# TD_Toolboard_V2.net
KiCad netlist of a schematic drawn in EAGLE
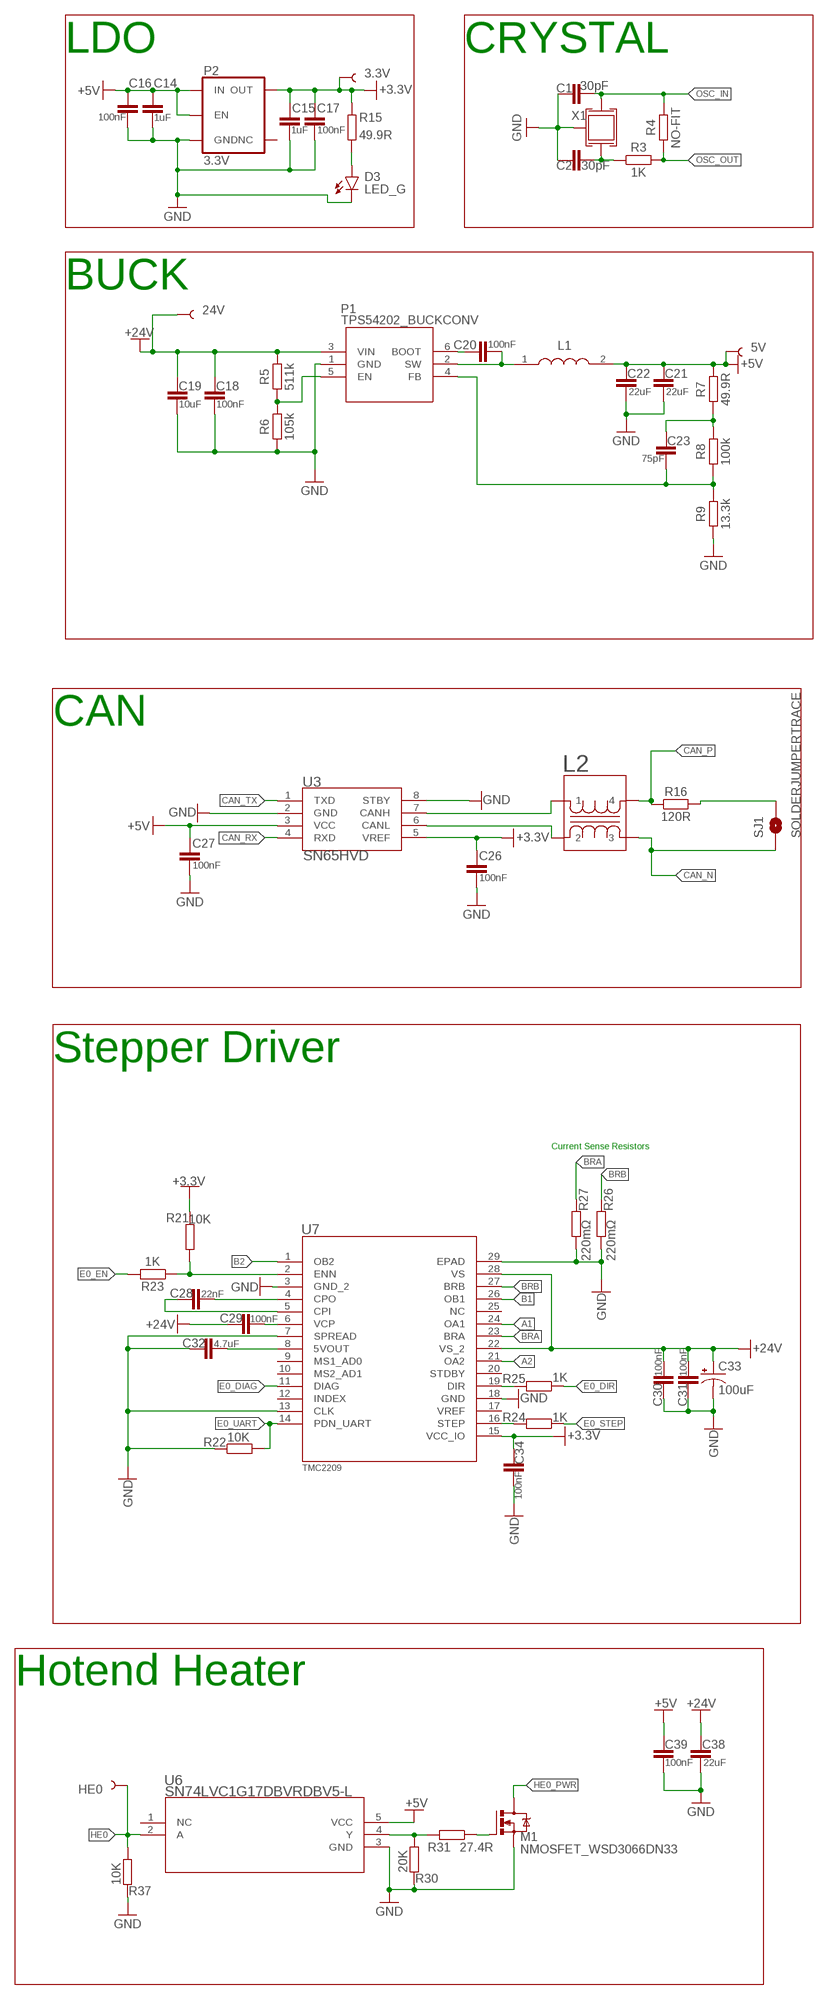
[diagram p0: schematic, sheet 1, part 1 of 2]
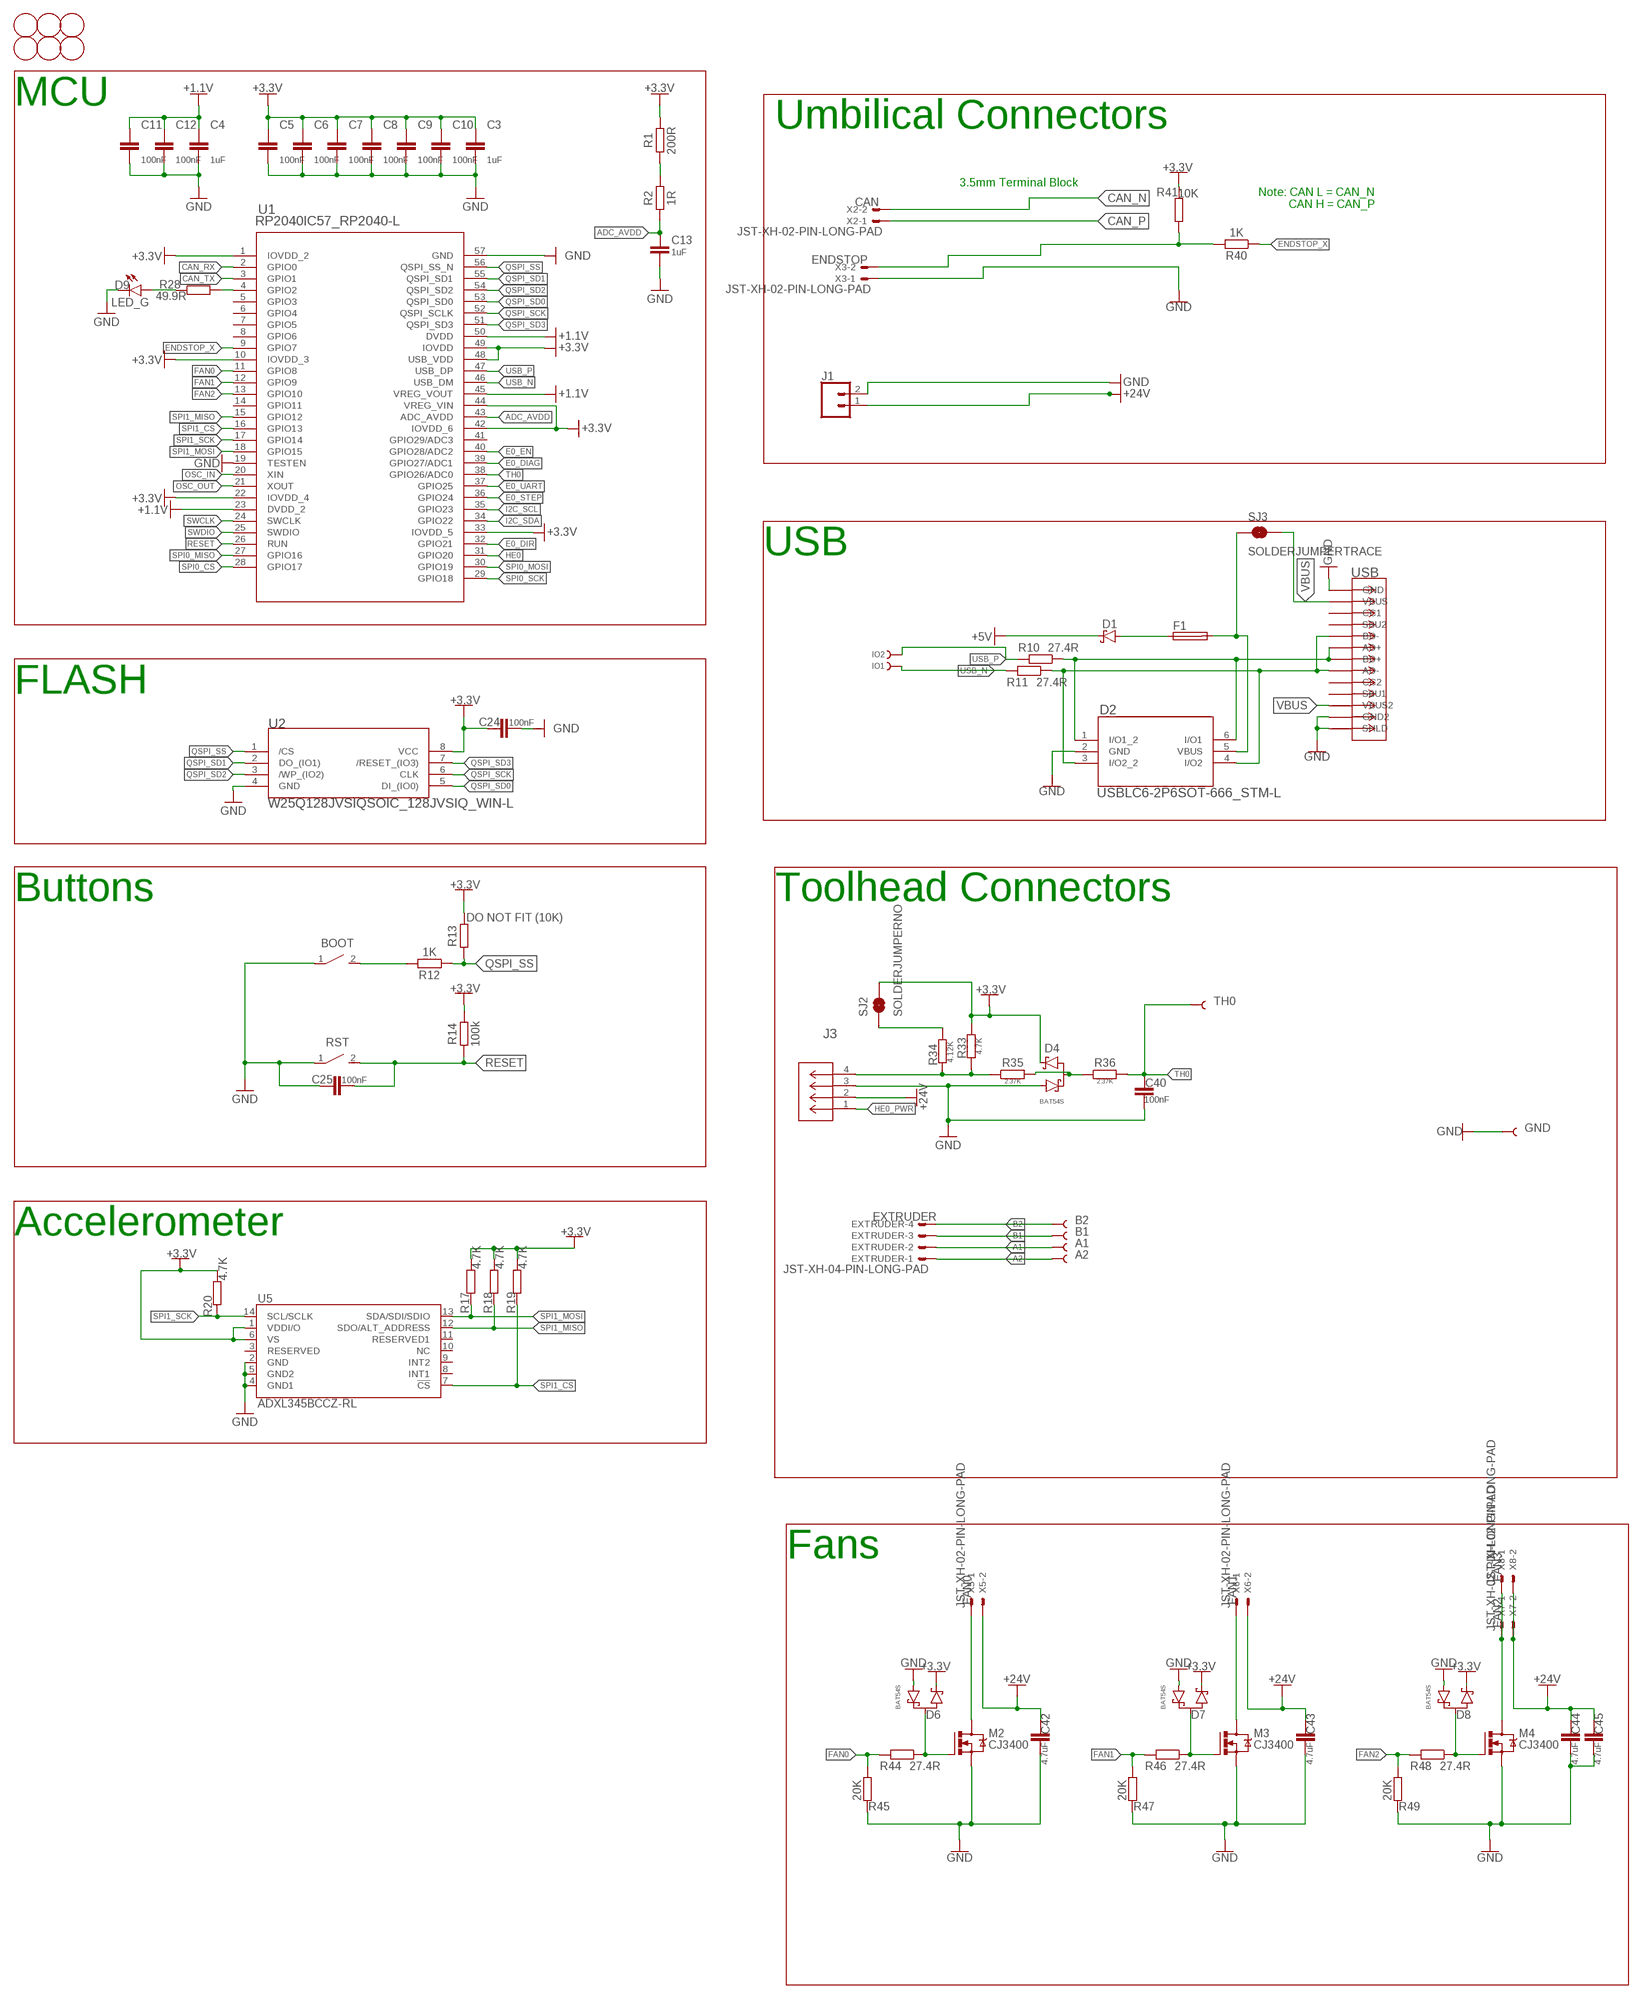
[diagram p1: schematic, sheet 1, part 2 of 2]

(export (version "E")
  (design (tool "Eeschema 10.0.6"))
  (components
    (comp (ref "3.3V")
      (value "TEST-POINT3X4")
      (footprint "eagle-import:PAD.03X.04")
      (libsource (lib "eagle-import") (part "TEST-POINT3X4"))
    )
    (comp (ref "5V")
      (value "TEST-POINT3X4")
      (footprint "eagle-import:PAD.03X.04")
      (libsource (lib "eagle-import") (part "TEST-POINT3X4"))
    )
    (comp (ref "24V")
      (value "TEST-POINT3X4")
      (footprint "eagle-import:PAD.03X.04")
      (libsource (lib "eagle-import") (part "TEST-POINT3X4"))
    )
    (comp (ref "A1")
      (value "TEST-POINT3X4")
      (footprint "eagle-import:PAD.03X.04")
      (libsource (lib "eagle-import") (part "TEST-POINT3X4"))
    )
    (comp (ref "A2")
      (value "TEST-POINT3X4")
      (footprint "eagle-import:PAD.03X.04")
      (libsource (lib "eagle-import") (part "TEST-POINT3X4"))
    )
    (comp (ref "B1")
      (value "TEST-POINT3X4")
      (footprint "eagle-import:PAD.03X.04")
      (libsource (lib "eagle-import") (part "TEST-POINT3X4"))
    )
    (comp (ref "B2")
      (value "TEST-POINT3X4")
      (footprint "eagle-import:PAD.03X.04")
      (libsource (lib "eagle-import") (part "TEST-POINT3X4"))
    )
    (comp (ref "BOOT")
      (value "B3U-1000P(M)-B")
      (footprint "eagle-import:B3U-1000P(M)-B")
      (fields (field (name "MANUFACTURER") "OMRON"))
      (libsource (lib "eagle-import") (part "B3U-X0001000P(M)-BB3U-1000P(M)-B"))
    )
    (comp (ref "C1")
      (value "30pF")
      (footprint "eagle-import:CAPC1005X60")
      (libsource (lib "eagle-import") (part "CCHIP-0402(1005-METRIC)_"))
    )
    (comp (ref "C2")
      (value "30pF")
      (footprint "eagle-import:CAPC1005X60")
      (libsource (lib "eagle-import") (part "CCHIP-0402(1005-METRIC)_"))
    )
    (comp (ref "C3")
      (value "1uF")
      (footprint "eagle-import:CAPC1005X60")
      (libsource (lib "eagle-import") (part "CCHIP-0402(1005-METRIC)_"))
    )
    (comp (ref "C4")
      (value "1uF")
      (footprint "eagle-import:CAPC1005X60")
      (libsource (lib "eagle-import") (part "CCHIP-0402(1005-METRIC)_"))
    )
    (comp (ref "C5")
      (value "100nF")
      (footprint "eagle-import:CAPC1005X60")
      (libsource (lib "eagle-import") (part "CCHIP-0402(1005-METRIC)_"))
    )
    (comp (ref "C6")
      (value "100nF")
      (footprint "eagle-import:CAPC1005X60")
      (libsource (lib "eagle-import") (part "CCHIP-0402(1005-METRIC)_"))
    )
    (comp (ref "C7")
      (value "100nF")
      (footprint "eagle-import:CAPC1005X60")
      (libsource (lib "eagle-import") (part "CCHIP-0402(1005-METRIC)_"))
    )
    (comp (ref "C8")
      (value "100nF")
      (footprint "eagle-import:CAPC1005X60")
      (libsource (lib "eagle-import") (part "CCHIP-0402(1005-METRIC)_"))
    )
    (comp (ref "C9")
      (value "100nF")
      (footprint "eagle-import:CAPC1005X60")
      (libsource (lib "eagle-import") (part "CCHIP-0402(1005-METRIC)_"))
    )
    (comp (ref "C10")
      (value "100nF")
      (footprint "eagle-import:CAPC1005X60")
      (libsource (lib "eagle-import") (part "CCHIP-0402(1005-METRIC)_"))
    )
    (comp (ref "C11")
      (value "100nF")
      (footprint "eagle-import:CAPC1005X60")
      (libsource (lib "eagle-import") (part "CCHIP-0402(1005-METRIC)_"))
    )
    (comp (ref "C12")
      (value "100nF")
      (footprint "eagle-import:CAPC1005X60")
      (libsource (lib "eagle-import") (part "CCHIP-0402(1005-METRIC)_"))
    )
    (comp (ref "C13")
      (value "1uF")
      (footprint "eagle-import:CAPC1005X60")
      (libsource (lib "eagle-import") (part "CCHIP-0402(1005-METRIC)_"))
    )
    (comp (ref "C14")
      (value "1uF")
      (footprint "eagle-import:CAPC1005X60")
      (libsource (lib "eagle-import") (part "CCHIP-0402(1005-METRIC)_"))
    )
    (comp (ref "C15")
      (value "1uF")
      (footprint "eagle-import:CAPC1005X60")
      (libsource (lib "eagle-import") (part "CCHIP-0402(1005-METRIC)_"))
    )
    (comp (ref "C16")
      (value "100nF")
      (footprint "eagle-import:CAPC1005X60")
      (libsource (lib "eagle-import") (part "CCHIP-0402(1005-METRIC)_"))
    )
    (comp (ref "C17")
      (value "100nF")
      (footprint "eagle-import:CAPC1005X60")
      (libsource (lib "eagle-import") (part "CCHIP-0402(1005-METRIC)_"))
    )
    (comp (ref "C18")
      (value "100nF")
      (footprint "eagle-import:CAPC1005X60")
      (libsource (lib "eagle-import") (part "CCHIP-0402(1005-METRIC)_"))
    )
    (comp (ref "C19")
      (value "10uF")
      (footprint "eagle-import:CAPC1608X85")
      (libsource (lib "eagle-import") (part "CCHIP-0603(1608-METRIC)_"))
    )
    (comp (ref "C20")
      (value "100nF")
      (footprint "eagle-import:CAPC1005X60")
      (libsource (lib "eagle-import") (part "CCHIP-0402(1005-METRIC)_"))
    )
    (comp (ref "C21")
      (value "22uF")
      (footprint "eagle-import:CAPC2012X110")
      (libsource (lib "eagle-import") (part "CCHIP-0805(2012-METRIC)_"))
    )
    (comp (ref "C22")
      (value "22uF")
      (footprint "eagle-import:CAPC2012X110")
      (libsource (lib "eagle-import") (part "CCHIP-0805(2012-METRIC)_"))
    )
    (comp (ref "C23")
      (value "75pF")
      (footprint "eagle-import:CAPC1005X60")
      (libsource (lib "eagle-import") (part "CCHIP-0402(1005-METRIC)_"))
    )
    (comp (ref "C24")
      (value "100nF")
      (footprint "eagle-import:CAPC1005X60")
      (libsource (lib "eagle-import") (part "CCHIP-0402(1005-METRIC)_"))
    )
    (comp (ref "C25")
      (value "100nF")
      (footprint "eagle-import:CAPC1005X60")
      (libsource (lib "eagle-import") (part "CCHIP-0402(1005-METRIC)_"))
    )
    (comp (ref "C26")
      (value "100nF")
      (footprint "eagle-import:CAPC1005X60")
      (libsource (lib "eagle-import") (part "CCHIP-0402(1005-METRIC)_"))
    )
    (comp (ref "C27")
      (value "100nF")
      (footprint "eagle-import:CAPC1005X60")
      (libsource (lib "eagle-import") (part "CCHIP-0402(1005-METRIC)_"))
    )
    (comp (ref "C28")
      (value "22nF")
      (footprint "eagle-import:CAPC1005X60")
      (libsource (lib "eagle-import") (part "CCHIP-0402(1005-METRIC)_"))
    )
    (comp (ref "C29")
      (value "100nF")
      (footprint "eagle-import:CAPC1005X60")
      (libsource (lib "eagle-import") (part "CCHIP-0402(1005-METRIC)_"))
    )
    (comp (ref "C30")
      (value "100nF")
      (footprint "eagle-import:CAPC1005X60")
      (libsource (lib "eagle-import") (part "CCHIP-0402(1005-METRIC)_"))
    )
    (comp (ref "C31")
      (value "100nF")
      (footprint "eagle-import:CAPC1005X60")
      (libsource (lib "eagle-import") (part "CCHIP-0402(1005-METRIC)_"))
    )
    (comp (ref "C32")
      (value "4.7uF")
      (footprint "eagle-import:CAPC1608X85")
      (libsource (lib "eagle-import") (part "CCHIP-0603(1608-METRIC)_"))
    )
    (comp (ref "C33")
      (value "100uF")
      (footprint "eagle-import:PANASONIC_D")
      (libsource (lib "eagle-import") (part "100UF-POLAR-25V-20%(ELEC)"))
    )
    (comp (ref "C34")
      (value "100nF")
      (footprint "eagle-import:CAPC1005X60")
      (libsource (lib "eagle-import") (part "CCHIP-0402(1005-METRIC)_"))
    )
    (comp (ref "C38")
      (value "22uF")
      (footprint "eagle-import:CAPC2012X110")
      (libsource (lib "eagle-import") (part "CCHIP-0805(2012-METRIC)_"))
    )
    (comp (ref "C39")
      (value "100nF")
      (footprint "eagle-import:CAPC1005X60")
      (libsource (lib "eagle-import") (part "CCHIP-0402(1005-METRIC)_"))
    )
    (comp (ref "C40")
      (value "100nF")
      (footprint "eagle-import:CAPC1005X60")
      (libsource (lib "eagle-import") (part "CCHIP-0402(1005-METRIC)_"))
    )
    (comp (ref "C42")
      (value "4.7uF")
      (footprint "eagle-import:CAPC1608X85")
      (libsource (lib "eagle-import") (part "CCHIP-0603(1608-METRIC)_"))
    )
    (comp (ref "C43")
      (value "4.7uF")
      (footprint "eagle-import:CAPC1608X85")
      (libsource (lib "eagle-import") (part "CCHIP-0603(1608-METRIC)_"))
    )
    (comp (ref "C44")
      (value "4.7uF")
      (footprint "eagle-import:CAPC1608X85")
      (libsource (lib "eagle-import") (part "CCHIP-0603(1608-METRIC)_"))
    )
    (comp (ref "C45")
      (value "4.7uF")
      (footprint "eagle-import:CAPC1608X85")
      (libsource (lib "eagle-import") (part "CCHIP-0603(1608-METRIC)_"))
    )
    (comp (ref "D1")
      (value "MBR0520LT1G")
      (footprint "eagle-import:SODFL3718X115")
      (fields (field (name "MANUFACTURER") "ON Semiconductor"))
      (libsource (lib "eagle-import") (part "SCHOTTKY_DO-219MBR0520LT1G"))
    )
    (comp (ref "D2")
      (value "USBLC6-2P6SOT-666_STM-L")
      (footprint "eagle-import:SOT-666_STM-L")
      (fields
        (field (name "MANUFACTURER_PART_NUMBER") "USBLC6-2P6")
        (field (name "COPYRIGHT") "Copyright (C) 2023 Ultra Librarian. All rights reserved.")
      )
      (libsource (lib "eagle-import") (part "USBLC6-2P6SOT-666_STM-L"))
    )
    (comp (ref "D3")
      (value "LED_G")
      (footprint "eagle-import:LEDC1608X35N_FLAT-G")
      (libsource (lib "eagle-import") (part "CHIP-FLAT-G_0603-0.35MM"))
    )
    (comp (ref "D4")
      (value "BAT54S")
      (footprint "eagle-import:SOT23")
      (libsource (lib "eagle-import") (part "BAT54S"))
    )
    (comp (ref "D6")
      (value "BAT54S")
      (footprint "eagle-import:SOT23")
      (libsource (lib "eagle-import") (part "BAT54S"))
    )
    (comp (ref "D7")
      (value "BAT54S")
      (footprint "eagle-import:SOT23")
      (libsource (lib "eagle-import") (part "BAT54S"))
    )
    (comp (ref "D8")
      (value "BAT54S")
      (footprint "eagle-import:SOT23")
      (libsource (lib "eagle-import") (part "BAT54S"))
    )
    (comp (ref "D9")
      (value "LED_G")
      (footprint "eagle-import:LEDC1608X35N_FLAT-G")
      (libsource (lib "eagle-import") (part "CHIP-FLAT-G_0603-0.35MM"))
    )
    (comp (ref "EXTRUDER")
      (value "JST-XH-04-PIN-LONG-PAD")
      (footprint "eagle-import:JST-XH-04-PACKAGE-LONG-PAD")
      (libsource (lib "eagle-import") (part "JST-XH-04-PIN-LONG-PAD"))
    )
    (comp (ref "F1")
      (value "FUSE_CHIP-0603(1608-METRIC)")
      (footprint "eagle-import:FUSC1608X60N")
      (libsource (lib "eagle-import") (part "FUSECHIP-0603(1608-METRIC)_"))
    )
    (comp (ref "FD1")
      (value "FIDUCIAL")
      (footprint "eagle-import:FIDUCIAL_1MM")
      (libsource (lib "eagle-import") (part "FIDUCIAL"))
    )
    (comp (ref "FD2")
      (value "FIDUCIAL")
      (footprint "eagle-import:FIDUCIAL_1MM")
      (libsource (lib "eagle-import") (part "FIDUCIAL"))
    )
    (comp (ref "FD3")
      (value "FIDUCIAL")
      (footprint "eagle-import:FIDUCIAL_1MM")
      (libsource (lib "eagle-import") (part "FIDUCIAL"))
    )
    (comp (ref "FD4")
      (value "FIDUCIAL")
      (footprint "eagle-import:FIDUCIAL_1MM")
      (libsource (lib "eagle-import") (part "FIDUCIAL"))
    )
    (comp (ref "FD5")
      (value "FIDUCIAL")
      (footprint "eagle-import:FIDUCIAL_1MM")
      (libsource (lib "eagle-import") (part "FIDUCIAL"))
    )
    (comp (ref "FD6")
      (value "FIDUCIAL")
      (footprint "eagle-import:FIDUCIAL_1MM")
      (libsource (lib "eagle-import") (part "FIDUCIAL"))
    )
    (comp (ref "GND")
      (value "TEST-POINT3X4")
      (footprint "eagle-import:PAD.03X.04")
      (libsource (lib "eagle-import") (part "TEST-POINT3X4"))
    )
    (comp (ref "HE0")
      (value "TEST-POINT3X4")
      (footprint "eagle-import:PAD.03X.04")
      (libsource (lib "eagle-import") (part "TEST-POINT3X4"))
    )
    (comp (ref "IO1")
      (value "TEST-POINT3")
      (footprint "eagle-import:PAD.03X.03")
      (libsource (lib "eagle-import") (part "TEST-POINT3"))
    )
    (comp (ref "IO2")
      (value "TEST-POINT3")
      (footprint "eagle-import:PAD.03X.03")
      (libsource (lib "eagle-import") (part "TEST-POINT3"))
    )
    (comp (ref "J1")
      (value "CONN_023.5MM")
      (footprint "eagle-import:SCREWTERMINAL-3.5MM-2")
      (libsource (lib "eagle-import") (part "CONN_023.5MM"))
    )
    (comp (ref "J3")
      (value "430450400CON_430450400_MOL")
      (footprint "eagle-import:CON_430450400_MOL")
      (fields
        (field (name "MANUFACTURER_PART_NUMBER") "430450400")
        (field (name "COPYRIGHT") "Copyright (C) 2023 Ultra Librarian. All rights reserved.")
      )
      (libsource (lib "eagle-import") (part "430450400CON_430450400_MOL"))
    )
    (comp (ref "L1")
      (value "ASPI-0630HI-100M-T157X7X4")
      (footprint "eagle-import:SMDRI74-680MT")
      (libsource (lib "eagle-import") (part "ASPI-0630HI-100M-T157X7X4"))
    )
    (comp (ref "L2")
      (value "ACM2012")
      (footprint "eagle-import:ACM2012_TDK")
      (fields
        (field (name "MANUFACTURER_PART_NUMBER") "ACM2012-201-2P-T002")
        (field (name "COPYRIGHT") "Copyright (C) 2023 Ultra Librarian. All rights reserved.")
      )
      (libsource (lib "eagle-import") (part "ACM2012-201-2P-T002ACM2012_TDK"))
    )
    (comp (ref "M1")
      (value "NMOSFET_WSD3066DN33")
      (footprint "eagle-import:NMOSFET_WSD3066DN33")
      (libsource (lib "eagle-import") (part "NMOSFET_WSD3066DN33"))
    )
    (comp (ref "M2")
      (value "CJ3400")
      (footprint "eagle-import:SOT23")
      (fields (field (name "MANUFACTURER") "ON Semiconductor") (field (name "MPN") "BSS123L"))
      (libsource (lib "eagle-import") (part "NMOSFET__SOT23-GSDBSS123"))
    )
    (comp (ref "M3")
      (value "CJ3400")
      (footprint "eagle-import:SOT23")
      (fields (field (name "MANUFACTURER") "ON Semiconductor") (field (name "MPN") "BSS123L"))
      (libsource (lib "eagle-import") (part "NMOSFET__SOT23-GSDBSS123"))
    )
    (comp (ref "M4")
      (value "CJ3400")
      (footprint "eagle-import:SOT23")
      (fields (field (name "MANUFACTURER") "ON Semiconductor") (field (name "MPN") "BSS123L"))
      (libsource (lib "eagle-import") (part "NMOSFET__SOT23-GSDBSS123"))
    )
    (comp (ref "P1")
      (value "TPS54202_BUCKCONV")
      (footprint "eagle-import:SOT-23-6")
      (libsource (lib "eagle-import") (part "TPS54202_BUCKCONV"))
    )
    (comp (ref "P2")
      (value "3.3V")
      (footprint "eagle-import:SOT23-5")
      (libsource (lib "eagle-import") (part "V_REG_AP2112K-3.3V"))
    )
    (comp (ref "R1")
      (value "200R")
      (footprint "eagle-import:RESC1005X40")
      (libsource (lib "eagle-import") (part "RCHIP-0402(1005-METRIC)_"))
    )
    (comp (ref "R2")
      (value "1R")
      (footprint "eagle-import:RESC1005X40")
      (libsource (lib "eagle-import") (part "RCHIP-0402(1005-METRIC)_"))
    )
    (comp (ref "R3")
      (value "1K")
      (footprint "eagle-import:RESC1005X40")
      (libsource (lib "eagle-import") (part "RCHIP-0402(1005-METRIC)_"))
    )
    (comp (ref "R4")
      (value "NO-FIT")
      (footprint "eagle-import:RESC1005X40")
      (libsource (lib "eagle-import") (part "RCHIP-0402(1005-METRIC)_"))
    )
    (comp (ref "R5")
      (value "511k")
      (footprint "eagle-import:RESC1005X40")
      (libsource (lib "eagle-import") (part "RCHIP-0402(1005-METRIC)_"))
    )
    (comp (ref "R6")
      (value "105k")
      (footprint "eagle-import:RESC1005X40")
      (libsource (lib "eagle-import") (part "RCHIP-0402(1005-METRIC)_"))
    )
    (comp (ref "R7")
      (value "49.9R")
      (footprint "eagle-import:RESC1005X40")
      (libsource (lib "eagle-import") (part "RCHIP-0402(1005-METRIC)_"))
    )
    (comp (ref "R8")
      (value "100k")
      (footprint "eagle-import:RESC1005X40")
      (libsource (lib "eagle-import") (part "RCHIP-0402(1005-METRIC)_"))
    )
    (comp (ref "R9")
      (value "13.3k")
      (footprint "eagle-import:RESC1005X40")
      (libsource (lib "eagle-import") (part "RCHIP-0402(1005-METRIC)_"))
    )
    (comp (ref "R10")
      (value "27.4R")
      (footprint "eagle-import:RESC1005X40")
      (libsource (lib "eagle-import") (part "RCHIP-0402(1005-METRIC)_"))
    )
    (comp (ref "R11")
      (value "27.4R")
      (footprint "eagle-import:RESC1005X40")
      (libsource (lib "eagle-import") (part "RCHIP-0402(1005-METRIC)_"))
    )
    (comp (ref "R12")
      (value "1K")
      (footprint "eagle-import:RESC1005X40")
      (libsource (lib "eagle-import") (part "RCHIP-0402(1005-METRIC)_"))
    )
    (comp (ref "R13")
      (value "DO NOT FIT (10K)")
      (footprint "eagle-import:RESC1005X40")
      (libsource (lib "eagle-import") (part "RCHIP-0402(1005-METRIC)_"))
    )
    (comp (ref "R14")
      (value "100k")
      (footprint "eagle-import:RESC1005X40")
      (libsource (lib "eagle-import") (part "RCHIP-0402(1005-METRIC)_"))
    )
    (comp (ref "R15")
      (value "49.9R")
      (footprint "eagle-import:RESC1005X40")
      (libsource (lib "eagle-import") (part "RCHIP-0402(1005-METRIC)_"))
    )
    (comp (ref "R16")
      (value "120R")
      (footprint "eagle-import:RESC1005X40")
      (libsource (lib "eagle-import") (part "RCHIP-0402(1005-METRIC)_"))
    )
    (comp (ref "R17")
      (value "4.7K")
      (footprint "eagle-import:RESC1005X40")
      (libsource (lib "eagle-import") (part "RCHIP-0402(1005-METRIC)_"))
    )
    (comp (ref "R18")
      (value "4.7K")
      (footprint "eagle-import:RESC1005X40")
      (libsource (lib "eagle-import") (part "RCHIP-0402(1005-METRIC)_"))
    )
    (comp (ref "R19")
      (value "4.7K")
      (footprint "eagle-import:RESC1005X40")
      (libsource (lib "eagle-import") (part "RCHIP-0402(1005-METRIC)_"))
    )
    (comp (ref "R20")
      (value "4.7K")
      (footprint "eagle-import:RESC1005X40")
      (libsource (lib "eagle-import") (part "RCHIP-0402(1005-METRIC)_"))
    )
    (comp (ref "R21")
      (value "10K")
      (footprint "eagle-import:RESC1005X40")
      (libsource (lib "eagle-import") (part "RCHIP-0402(1005-METRIC)_"))
    )
    (comp (ref "R22")
      (value "10K")
      (footprint "eagle-import:RESC1005X40")
      (libsource (lib "eagle-import") (part "RCHIP-0402(1005-METRIC)_"))
    )
    (comp (ref "R23")
      (value "1K")
      (footprint "eagle-import:RESC1005X40")
      (libsource (lib "eagle-import") (part "RCHIP-0402(1005-METRIC)_"))
    )
    (comp (ref "R24")
      (value "1K")
      (footprint "eagle-import:RESC1005X40")
      (libsource (lib "eagle-import") (part "RCHIP-0402(1005-METRIC)_"))
    )
    (comp (ref "R25")
      (value "1K")
      (footprint "eagle-import:RESC1005X40")
      (libsource (lib "eagle-import") (part "RCHIP-0402(1005-METRIC)_"))
    )
    (comp (ref "R26")
      (value "220mΩ")
      (footprint "eagle-import:RESC1005X40")
      (libsource (lib "eagle-import") (part "RCHIP-0402(1005-METRIC)_"))
    )
    (comp (ref "R27")
      (value "220mΩ")
      (footprint "eagle-import:RESC1005X40")
      (libsource (lib "eagle-import") (part "RCHIP-0402(1005-METRIC)_"))
    )
    (comp (ref "R28")
      (value "49.9R")
      (footprint "eagle-import:RESC1005X40")
      (libsource (lib "eagle-import") (part "RCHIP-0402(1005-METRIC)_"))
    )
    (comp (ref "R30")
      (value "20K")
      (footprint "eagle-import:RESC1005X40")
      (libsource (lib "eagle-import") (part "RCHIP-0402(1005-METRIC)_"))
    )
    (comp (ref "R31")
      (value "27.4R")
      (footprint "eagle-import:RESC1005X40")
      (libsource (lib "eagle-import") (part "RCHIP-0402(1005-METRIC)_"))
    )
    (comp (ref "R33")
      (value "4.7K")
      (footprint "eagle-import:RESC1005X40")
      (libsource (lib "eagle-import") (part "RCHIP-0402(1005-METRIC)_"))
    )
    (comp (ref "R34")
      (value "4.12K")
      (footprint "eagle-import:RESC1005X40")
      (libsource (lib "eagle-import") (part "RCHIP-0402(1005-METRIC)_"))
    )
    (comp (ref "R35")
      (value "2.37K")
      (footprint "eagle-import:RESC1005X40")
      (libsource (lib "eagle-import") (part "RCHIP-0402(1005-METRIC)_"))
    )
    (comp (ref "R36")
      (value "2.37K")
      (footprint "eagle-import:RESC1005X40")
      (libsource (lib "eagle-import") (part "RCHIP-0402(1005-METRIC)_"))
    )
    (comp (ref "R37")
      (value "10K")
      (footprint "eagle-import:RESC1005X40")
      (libsource (lib "eagle-import") (part "RCHIP-0402(1005-METRIC)_"))
    )
    (comp (ref "R40")
      (value "1K")
      (footprint "eagle-import:RESC1005X40")
      (libsource (lib "eagle-import") (part "RCHIP-0402(1005-METRIC)_"))
    )
    (comp (ref "R41")
      (value "10K")
      (footprint "eagle-import:RESC1005X40")
      (libsource (lib "eagle-import") (part "RCHIP-0402(1005-METRIC)_"))
    )
    (comp (ref "R44")
      (value "27.4R")
      (footprint "eagle-import:RESC1005X40")
      (libsource (lib "eagle-import") (part "RCHIP-0402(1005-METRIC)_"))
    )
    (comp (ref "R45")
      (value "20K")
      (footprint "eagle-import:RESC1005X40")
      (libsource (lib "eagle-import") (part "RCHIP-0402(1005-METRIC)_"))
    )
    (comp (ref "R46")
      (value "27.4R")
      (footprint "eagle-import:RESC1005X40")
      (libsource (lib "eagle-import") (part "RCHIP-0402(1005-METRIC)_"))
    )
    (comp (ref "R47")
      (value "20K")
      (footprint "eagle-import:RESC1005X40")
      (libsource (lib "eagle-import") (part "RCHIP-0402(1005-METRIC)_"))
    )
    (comp (ref "R48")
      (value "27.4R")
      (footprint "eagle-import:RESC1005X40")
      (libsource (lib "eagle-import") (part "RCHIP-0402(1005-METRIC)_"))
    )
    (comp (ref "R49")
      (value "20K")
      (footprint "eagle-import:RESC1005X40")
      (libsource (lib "eagle-import") (part "RCHIP-0402(1005-METRIC)_"))
    )
    (comp (ref "RST")
      (value "B3U-1000P(M)-B")
      (footprint "eagle-import:B3U-1000P(M)-B")
      (fields (field (name "MANUFACTURER") "OMRON"))
      (libsource (lib "eagle-import") (part "B3U-X0001000P(M)-BB3U-1000P(M)-B"))
    )
    (comp (ref "SJ1")
      (value "SOLDERJUMPERTRACE")
      (footprint "eagle-import:SJ_2S-TRACE")
      (libsource (lib "eagle-import") (part "SOLDERJUMPERTRACE"))
    )
    (comp (ref "SJ2")
      (value "SOLDERJUMPERNO")
      (footprint "eagle-import:SJ_2S-NO")
      (libsource (lib "eagle-import") (part "SOLDERJUMPERNO"))
    )
    (comp (ref "SJ3")
      (value "SOLDERJUMPERTRACE")
      (footprint "eagle-import:SJ_2S-TRACE")
      (libsource (lib "eagle-import") (part "SOLDERJUMPERTRACE"))
    )
    (comp (ref "TH0")
      (value "TEST-POINT3X4")
      (footprint "eagle-import:PAD.03X.04")
      (libsource (lib "eagle-import") (part "TEST-POINT3X4"))
    )
    (comp (ref "U1")
      (value "RP2040IC57_RP2040-L")
      (footprint "eagle-import:IC57_RP2040-L")
      (fields
        (field (name "MANUFACTURER_PART_NUMBER") "RP2040")
        (field (name "COPYRIGHT") "Copyright (C) 2023 Ultra Librarian. All rights reserved.")
      )
      (libsource (lib "eagle-import") (part "RP2040IC57_RP2040-L"))
    )
    (comp (ref "U2")
      (value "W25Q128JVSIQSOIC_128JVSIQ_WIN-L")
      (footprint "eagle-import:SOIC_128JVSIQ_WIN-L")
      (fields
        (field (name "MANUFACTURER_PART_NUMBER") "W25Q128JVSIQ")
        (field (name "COPYRIGHT") "Copyright (C) 2023 Ultra Librarian. All rights reserved.")
      )
      (libsource (lib "eagle-import") (part "W25Q128JVSIQSOIC_128JVSIQ_WIN-L"))
    )
    (comp (ref "U3")
      (value "SN65HVD")
      (footprint "eagle-import:D8-L")
      (fields
        (field (name "MANUFACTURER_PART_NUMBER") "SN65HVD1050DR")
        (field (name "COPYRIGHT") "Copyright (C) 2023 Ultra Librarian. All rights reserved.")
      )
      (libsource (lib "eagle-import") (part "SN65HVD1050DRD8-L"))
    )
    (comp (ref "U5")
      (value "ADXL345BCCZ-RL")
      (footprint "eagle-import:ADXL345_LGA14")
      (fields (field (name "MANUFACTURER") "ANALOG DEVICES"))
      (libsource (lib "eagle-import") (part "ADXL345BCCZ-RL"))
    )
    (comp (ref "U6")
      (value "SN74LVC1G17DBVRDBV5-L")
      (footprint "eagle-import:DBV5-L")
      (fields
        (field (name "MANUFACTURER_PART_NUMBER") "SN74LVC1G17DBVR")
        (field (name "COPYRIGHT") "Copyright (C) 2023 Ultra Librarian. All rights reserved.")
      )
      (libsource (lib "eagle-import") (part "SN74LVC1G17DBVRDBV5-L"))
    )
    (comp (ref "U7")
      (value "TMC2209")
      (footprint "eagle-import:QFN28_5X5_3X8_EPAD_TRI")
      (fields
        (field (name "MANUFACTURER_PART_NUMBER") "TMC2209-LA-T")
        (field (name "COPYRIGHT") "Copyright (C) 2023 Ultra Librarian. All rights reserved.")
      )
      (libsource (lib "eagle-import") (part "TMC2209-LA-TQFN28_5X5_3X8_EPAD_TRI"))
    )
    (comp (ref "USB")
      (value "USB-C(DX07S016JA1R1500)")
      (footprint "eagle-import:CONN12_016JA1R1500_JAE")
      (fields
        (field (name "MANUFACTURER_PART_NUMBER") "DX07S016JA1R1500")
        (field (name "COPYRIGHT") "Copyright (C) 2018 Accelerated Designs. All rights reserved")
      )
      (libsource (lib "eagle-import") (part "USB-C(DX07S016JA1R1500)"))
    )
    (comp (ref "X1")
      (value "CRYSTAL_TAXM12M4RLBDDT2T_3225")
      (footprint "eagle-import:CRYSTAL_3225")
      (libsource (lib "eagle-import") (part "CRYSTAL_TAXM12M4RLBDDT2T_3225"))
    )
    (comp (ref "X2")
      (value "JST-XH-02-PIN-LONG-PAD")
      (footprint "eagle-import:JST-XH-02-PACKAGE-LONG-PAD")
      (libsource (lib "eagle-import") (part "JST-XH-02-PIN-LONG-PAD"))
    )
    (comp (ref "X3")
      (value "JST-XH-02-PIN-LONG-PAD")
      (footprint "eagle-import:JST-XH-02-PACKAGE-LONG-PAD")
      (libsource (lib "eagle-import") (part "JST-XH-02-PIN-LONG-PAD"))
    )
    (comp (ref "X5")
      (value "JST-XH-02-PIN-LONG-PAD")
      (footprint "eagle-import:JST-XH-02-PACKAGE-LONG-PAD")
      (libsource (lib "eagle-import") (part "JST-XH-02-PIN-LONG-PAD"))
    )
    (comp (ref "X6")
      (value "JST-XH-02-PIN-LONG-PAD")
      (footprint "eagle-import:JST-XH-02-PACKAGE-LONG-PAD")
      (libsource (lib "eagle-import") (part "JST-XH-02-PIN-LONG-PAD"))
    )
    (comp (ref "X7")
      (value "JST-XH-02-PIN-LONG-PAD")
      (footprint "eagle-import:JST-XH-02-PACKAGE-LONG-PAD")
      (libsource (lib "eagle-import") (part "JST-XH-02-PIN-LONG-PAD"))
    )
    (comp (ref "X8")
      (value "JST-XH-02-PIN-LONG-PAD")
      (footprint "eagle-import:JST-XH-02-PACKAGE-LONG-PAD")
      (libsource (lib "eagle-import") (part "JST-XH-02-PIN-LONG-PAD"))
    )
  )
  (nets
    (net (code "1") (name "+1.1V") (class "Default")
      (node (ref "C11") (pin "1") (pinfunction "1_1") (pintype "passive"))
      (node (ref "C12") (pin "1") (pinfunction "1_1") (pintype "passive"))
      (node (ref "C4") (pin "1") (pinfunction "1_1") (pintype "passive"))
      (node (ref "U1") (pin "23") (pinfunction "DVDD_2_23") (pintype "power_in"))
      (node (ref "U1") (pin "45") (pinfunction "VREG_VOUT_45") (pintype "output"))
      (node (ref "U1") (pin "50") (pinfunction "DVDD_50") (pintype "power_in"))
    )
    (net (code "2") (name "+3.3V") (class "Default")
      (node (ref "3.3V") (pin "P$1") (pinfunction "1_P$1") (pintype "bidirectional"))
      (node (ref "C10") (pin "1") (pinfunction "1_1") (pintype "passive"))
      (node (ref "C15") (pin "1") (pinfunction "1_1") (pintype "passive"))
      (node (ref "C17") (pin "1") (pinfunction "1_1") (pintype "passive"))
      (node (ref "C24") (pin "1") (pinfunction "1_1") (pintype "passive"))
      (node (ref "C26") (pin "1") (pinfunction "1_1") (pintype "passive"))
      (node (ref "C3") (pin "1") (pinfunction "1_1") (pintype "passive"))
      (node (ref "C34") (pin "1") (pinfunction "1_1") (pintype "passive"))
      (node (ref "C5") (pin "1") (pinfunction "1_1") (pintype "passive"))
      (node (ref "C6") (pin "1") (pinfunction "1_1") (pintype "passive"))
      (node (ref "C7") (pin "1") (pinfunction "1_1") (pintype "passive"))
      (node (ref "C8") (pin "1") (pinfunction "1_1") (pintype "passive"))
      (node (ref "C9") (pin "1") (pinfunction "1_1") (pintype "passive"))
      (node (ref "D4") (pin "2") (pinfunction "2_2") (pintype "passive"))
      (node (ref "D6") (pin "2") (pinfunction "2_2") (pintype "passive"))
      (node (ref "D7") (pin "2") (pinfunction "2_2") (pintype "passive"))
      (node (ref "D8") (pin "2") (pinfunction "2_2") (pintype "passive"))
      (node (ref "P2") (pin "5") (pinfunction "OUT_5") (pintype "passive"))
      (node (ref "R1") (pin "2") (pinfunction "2_2") (pintype "passive"))
      (node (ref "R13") (pin "2") (pinfunction "2_2") (pintype "passive"))
      (node (ref "R14") (pin "2") (pinfunction "2_2") (pintype "passive"))
      (node (ref "R15") (pin "2") (pinfunction "2_2") (pintype "passive"))
      (node (ref "R17") (pin "2") (pinfunction "2_2") (pintype "passive"))
      (node (ref "R18") (pin "2") (pinfunction "2_2") (pintype "passive"))
      (node (ref "R19") (pin "2") (pinfunction "2_2") (pintype "passive"))
      (node (ref "R20") (pin "2") (pinfunction "2_2") (pintype "passive"))
      (node (ref "R21") (pin "1") (pinfunction "1_1") (pintype "passive"))
      (node (ref "R33") (pin "2") (pinfunction "2_2") (pintype "passive"))
      (node (ref "R41") (pin "1") (pinfunction "1_1") (pintype "passive"))
      (node (ref "SJ2") (pin "2") (pinfunction "2_2") (pintype "passive"))
      (node (ref "U1") (pin "1") (pinfunction "IOVDD_2_1") (pintype "power_in"))
      (node (ref "U1") (pin "10") (pinfunction "IOVDD_3_10") (pintype "power_in"))
      (node (ref "U1") (pin "22") (pinfunction "IOVDD_4_22") (pintype "power_in"))
      (node (ref "U1") (pin "33") (pinfunction "IOVDD_5_33") (pintype "power_in"))
      (node (ref "U1") (pin "42") (pinfunction "IOVDD_6_42") (pintype "power_in"))
      (node (ref "U1") (pin "44") (pinfunction "VREG_VIN_44") (pintype "passive"))
      (node (ref "U1") (pin "48") (pinfunction "USB_VDD_48") (pintype "power_in"))
      (node (ref "U1") (pin "49") (pinfunction "IOVDD_49") (pintype "power_in"))
      (node (ref "U2") (pin "8") (pinfunction "VCC_8") (pintype "power_in"))
      (node (ref "U3") (pin "5") (pinfunction "VREF_5") (pintype "power_in"))
      (node (ref "U5") (pin "1") (pinfunction "VDDI/O_1") (pintype "bidirectional"))
      (node (ref "U5") (pin "6") (pinfunction "VS_6") (pintype "bidirectional"))
      (node (ref "U7") (pin "15") (pinfunction "VCC_IO_15") (pintype "power_in"))
    )
    (net (code "3") (name "+5V") (class "Default")
      (node (ref "5V") (pin "P$1") (pinfunction "1_P$1") (pintype "bidirectional"))
      (node (ref "C14") (pin "1") (pinfunction "1_1") (pintype "passive"))
      (node (ref "C16") (pin "1") (pinfunction "1_1") (pintype "passive"))
      (node (ref "C21") (pin "1") (pinfunction "1_1") (pintype "passive"))
      (node (ref "C22") (pin "1") (pinfunction "1_1") (pintype "passive"))
      (node (ref "C27") (pin "1") (pinfunction "1_1") (pintype "passive"))
      (node (ref "C39") (pin "1") (pinfunction "1_1") (pintype "passive"))
      (node (ref "D1") (pin "1") (pinfunction "C_1") (pintype "passive"))
      (node (ref "L1") (pin "2") (pinfunction "2_2") (pintype "bidirectional"))
      (node (ref "P2") (pin "1") (pinfunction "IN_1") (pintype "input"))
      (node (ref "P2") (pin "3") (pinfunction "EN_3") (pintype "input"))
      (node (ref "R7") (pin "2") (pinfunction "2_2") (pintype "passive"))
      (node (ref "U3") (pin "3") (pinfunction "VCC_3") (pintype "power_in"))
      (node (ref "U6") (pin "5") (pinfunction "VCC_5") (pintype "power_in"))
    )
    (net (code "4") (name "+24V") (class "Default")
      (node (ref "24V") (pin "P$1") (pinfunction "1_P$1") (pintype "bidirectional"))
      (node (ref "C18") (pin "1") (pinfunction "1_1") (pintype "passive"))
      (node (ref "C19") (pin "1") (pinfunction "1_1") (pintype "passive"))
      (node (ref "C29") (pin "1") (pinfunction "1_1") (pintype "passive"))
      (node (ref "C30") (pin "2") (pinfunction "2_2") (pintype "passive"))
      (node (ref "C31") (pin "2") (pinfunction "2_2") (pintype "passive"))
      (node (ref "C33") (pin "+") (pinfunction "+_+") (pintype "passive"))
      (node (ref "C38") (pin "1") (pinfunction "1_1") (pintype "passive"))
      (node (ref "C42") (pin "1") (pinfunction "1_1") (pintype "passive"))
      (node (ref "C43") (pin "1") (pinfunction "1_1") (pintype "passive"))
      (node (ref "C44") (pin "1") (pinfunction "1_1") (pintype "passive"))
      (node (ref "C45") (pin "1") (pinfunction "1_1") (pintype "passive"))
      (node (ref "J1") (pin "1") (pinfunction "1_1") (pintype "passive"))
      (node (ref "J3") (pin "2") (pinfunction "2_2") (pintype "passive"))
      (node (ref "P1") (pin "3") (pinfunction "VIN_3") (pintype "bidirectional"))
      (node (ref "R5") (pin "2") (pinfunction "2_2") (pintype "passive"))
      (node (ref "U7") (pin "22") (pinfunction "VS_2_22") (pintype "power_in"))
      (node (ref "U7") (pin "28") (pinfunction "VS_28") (pintype "power_in"))
      (node (ref "X5") (pin "2") (pinfunction "S_2") (pintype "passive"))
      (node (ref "X6") (pin "2") (pinfunction "S_2") (pintype "passive"))
      (node (ref "X7") (pin "2") (pinfunction "S_2") (pintype "passive"))
      (node (ref "X8") (pin "2") (pinfunction "S_2") (pintype "passive"))
    )
    (net (code "5") (name "A1") (class "Default")
      (node (ref "A1") (pin "P$1") (pinfunction "1_P$1") (pintype "bidirectional"))
      (node (ref "EXTRUDER") (pin "2") (pinfunction "S_2") (pintype "passive"))
      (node (ref "U7") (pin "24") (pinfunction "OA1_24") (pintype "output"))
    )
    (net (code "6") (name "A2") (class "Default")
      (node (ref "A2") (pin "P$1") (pinfunction "1_P$1") (pintype "bidirectional"))
      (node (ref "EXTRUDER") (pin "1") (pinfunction "S_1") (pintype "passive"))
      (node (ref "U7") (pin "21") (pinfunction "OA2_21") (pintype "output"))
    )
    (net (code "7") (name "ADC_AVDD") (class "Default")
      (node (ref "C13") (pin "1") (pinfunction "1_1") (pintype "passive"))
      (node (ref "R2") (pin "1") (pinfunction "1_1") (pintype "passive"))
      (node (ref "U1") (pin "43") (pinfunction "ADC_AVDD_43") (pintype "power_in"))
    )
    (net (code "8") (name "B1") (class "Default")
      (node (ref "B1") (pin "P$1") (pinfunction "1_P$1") (pintype "bidirectional"))
      (node (ref "EXTRUDER") (pin "3") (pinfunction "S_3") (pintype "passive"))
      (node (ref "U7") (pin "26") (pinfunction "OB1_26") (pintype "output"))
    )
    (net (code "9") (name "B2") (class "Default")
      (node (ref "B2") (pin "P$1") (pinfunction "1_P$1") (pintype "bidirectional"))
      (node (ref "EXTRUDER") (pin "4") (pinfunction "S_4") (pintype "passive"))
      (node (ref "U7") (pin "1") (pinfunction "OB2_1") (pintype "output"))
    )
    (net (code "10") (name "BRA") (class "Default")
      (node (ref "R27") (pin "2") (pinfunction "2_2") (pintype "passive"))
      (node (ref "U7") (pin "23") (pinfunction "BRA_23") (pintype "passive"))
    )
    (net (code "11") (name "BRB") (class "Default")
      (node (ref "R26") (pin "2") (pinfunction "2_2") (pintype "passive"))
      (node (ref "U7") (pin "27") (pinfunction "BRB_27") (pintype "passive"))
    )
    (net (code "12") (name "CAN_N") (class "Default")
      (node (ref "L2") (pin "3") (pinfunction "3_3") (pintype "passive"))
      (node (ref "SJ1") (pin "1") (pinfunction "1_1") (pintype "passive"))
      (node (ref "X2") (pin "2") (pinfunction "S_2") (pintype "passive"))
    )
    (net (code "13") (name "CAN_P") (class "Default")
      (node (ref "L2") (pin "4") (pinfunction "4_4") (pintype "passive"))
      (node (ref "R16") (pin "1") (pinfunction "1_1") (pintype "passive"))
      (node (ref "X2") (pin "1") (pinfunction "S_1") (pintype "passive"))
    )
    (net (code "14") (name "CAN_RX") (class "Default")
      (node (ref "U1") (pin "2") (pinfunction "GPIO0_2") (pintype "bidirectional"))
      (node (ref "U3") (pin "4") (pinfunction "RXD_4") (pintype "output"))
    )
    (net (code "15") (name "CAN_TX") (class "Default")
      (node (ref "U1") (pin "3") (pinfunction "GPIO1_3") (pintype "bidirectional"))
      (node (ref "U3") (pin "1") (pinfunction "TXD_1") (pintype "input"))
    )
    (net (code "16") (name "E0_DIAG") (class "Default")
      (node (ref "U1") (pin "39") (pinfunction "GPIO27/ADC1_39") (pintype "bidirectional"))
      (node (ref "U7") (pin "11") (pinfunction "DIAG_11") (pintype "output"))
    )
    (net (code "17") (name "E0_DIR") (class "Default")
      (node (ref "R25") (pin "1") (pinfunction "1_1") (pintype "passive"))
      (node (ref "U1") (pin "32") (pinfunction "GPIO21_32") (pintype "bidirectional"))
    )
    (net (code "18") (name "E0_EN") (class "Default")
      (node (ref "R23") (pin "2") (pinfunction "2_2") (pintype "passive"))
      (node (ref "U1") (pin "40") (pinfunction "GPIO28/ADC2_40") (pintype "bidirectional"))
    )
    (net (code "19") (name "E0_STEP") (class "Default")
      (node (ref "R24") (pin "1") (pinfunction "1_1") (pintype "passive"))
      (node (ref "U1") (pin "36") (pinfunction "GPIO24_36") (pintype "bidirectional"))
    )
    (net (code "20") (name "E0_UART") (class "Default")
      (node (ref "R22") (pin "2") (pinfunction "2_2") (pintype "passive"))
      (node (ref "U1") (pin "37") (pinfunction "GPIO25_37") (pintype "bidirectional"))
      (node (ref "U7") (pin "14") (pinfunction "PDN_UART_14") (pintype "bidirectional"))
    )
    (net (code "21") (name "ENDSTOP_X") (class "Default")
      (node (ref "R40") (pin "1") (pinfunction "1_1") (pintype "passive"))
      (node (ref "U1") (pin "9") (pinfunction "GPIO7_9") (pintype "bidirectional"))
    )
    (net (code "22") (name "FAN0") (class "Default")
      (node (ref "R44") (pin "2") (pinfunction "2_2") (pintype "passive"))
      (node (ref "R45") (pin "2") (pinfunction "2_2") (pintype "passive"))
      (node (ref "U1") (pin "11") (pinfunction "GPIO8_11") (pintype "bidirectional"))
    )
    (net (code "23") (name "FAN1") (class "Default")
      (node (ref "R46") (pin "2") (pinfunction "2_2") (pintype "passive"))
      (node (ref "R47") (pin "2") (pinfunction "2_2") (pintype "passive"))
      (node (ref "U1") (pin "12") (pinfunction "GPIO9_12") (pintype "bidirectional"))
    )
    (net (code "24") (name "FAN2") (class "Default")
      (node (ref "R48") (pin "2") (pinfunction "2_2") (pintype "passive"))
      (node (ref "R49") (pin "2") (pinfunction "2_2") (pintype "passive"))
      (node (ref "U1") (pin "13") (pinfunction "GPIO10_13") (pintype "bidirectional"))
    )
    (net (code "25") (name "GND") (class "Default")
      (node (ref "BOOT") (pin "1") (pinfunction "1_1") (pintype "bidirectional"))
      (node (ref "C1") (pin "2") (pinfunction "2_2") (pintype "passive"))
      (node (ref "C10") (pin "2") (pinfunction "2_2") (pintype "passive"))
      (node (ref "C11") (pin "2") (pinfunction "2_2") (pintype "passive"))
      (node (ref "C12") (pin "2") (pinfunction "2_2") (pintype "passive"))
      (node (ref "C13") (pin "2") (pinfunction "2_2") (pintype "passive"))
      (node (ref "C14") (pin "2") (pinfunction "2_2") (pintype "passive"))
      (node (ref "C15") (pin "2") (pinfunction "2_2") (pintype "passive"))
      (node (ref "C16") (pin "2") (pinfunction "2_2") (pintype "passive"))
      (node (ref "C17") (pin "2") (pinfunction "2_2") (pintype "passive"))
      (node (ref "C18") (pin "2") (pinfunction "2_2") (pintype "passive"))
      (node (ref "C19") (pin "2") (pinfunction "2_2") (pintype "passive"))
      (node (ref "C2") (pin "1") (pinfunction "1_1") (pintype "passive"))
      (node (ref "C21") (pin "2") (pinfunction "2_2") (pintype "passive"))
      (node (ref "C22") (pin "2") (pinfunction "2_2") (pintype "passive"))
      (node (ref "C24") (pin "2") (pinfunction "2_2") (pintype "passive"))
      (node (ref "C25") (pin "1") (pinfunction "1_1") (pintype "passive"))
      (node (ref "C26") (pin "2") (pinfunction "2_2") (pintype "passive"))
      (node (ref "C27") (pin "2") (pinfunction "2_2") (pintype "passive"))
      (node (ref "C3") (pin "2") (pinfunction "2_2") (pintype "passive"))
      (node (ref "C30") (pin "1") (pinfunction "1_1") (pintype "passive"))
      (node (ref "C31") (pin "1") (pinfunction "1_1") (pintype "passive"))
      (node (ref "C32") (pin "1") (pinfunction "1_1") (pintype "passive"))
      (node (ref "C33") (pin "-") (pinfunction "-_-") (pintype "passive"))
      (node (ref "C34") (pin "2") (pinfunction "2_2") (pintype "passive"))
      (node (ref "C38") (pin "2") (pinfunction "2_2") (pintype "passive"))
      (node (ref "C39") (pin "2") (pinfunction "2_2") (pintype "passive"))
      (node (ref "C4") (pin "2") (pinfunction "2_2") (pintype "passive"))
      (node (ref "C40") (pin "2") (pinfunction "2_2") (pintype "passive"))
      (node (ref "C42") (pin "2") (pinfunction "2_2") (pintype "passive"))
      (node (ref "C43") (pin "2") (pinfunction "2_2") (pintype "passive"))
      (node (ref "C44") (pin "2") (pinfunction "2_2") (pintype "passive"))
      (node (ref "C45") (pin "2") (pinfunction "2_2") (pintype "passive"))
      (node (ref "C5") (pin "2") (pinfunction "2_2") (pintype "passive"))
      (node (ref "C6") (pin "2") (pinfunction "2_2") (pintype "passive"))
      (node (ref "C7") (pin "2") (pinfunction "2_2") (pintype "passive"))
      (node (ref "C8") (pin "2") (pinfunction "2_2") (pintype "passive"))
      (node (ref "C9") (pin "2") (pinfunction "2_2") (pintype "passive"))
      (node (ref "D2") (pin "2") (pinfunction "GND_2") (pintype "power_in"))
      (node (ref "D3") (pin "C") (pinfunction "C_C") (pintype "passive"))
      (node (ref "D4") (pin "1") (pinfunction "1_1") (pintype "passive"))
      (node (ref "D6") (pin "1") (pinfunction "1_1") (pintype "passive"))
      (node (ref "D7") (pin "1") (pinfunction "1_1") (pintype "passive"))
      (node (ref "D8") (pin "1") (pinfunction "1_1") (pintype "passive"))
      (node (ref "D9") (pin "C") (pinfunction "C_C") (pintype "passive"))
      (node (ref "GND") (pin "P$1") (pinfunction "1_P$1") (pintype "bidirectional"))
      (node (ref "J1") (pin "2") (pinfunction "2_2") (pintype "passive"))
      (node (ref "J3") (pin "3") (pinfunction "3_3") (pintype "passive"))
      (node (ref "M1") (pin "P$1") (pinfunction "S_P$1") (pintype "passive"))
      (node (ref "M1") (pin "P$2") (pinfunction "S_P$2") (pintype "passive"))
      (node (ref "M1") (pin "P$3") (pinfunction "S_P$3") (pintype "passive"))
      (node (ref "M2") (pin "2") (pinfunction "S_2") (pintype "passive"))
      (node (ref "M3") (pin "2") (pinfunction "S_2") (pintype "passive"))
      (node (ref "M4") (pin "2") (pinfunction "S_2") (pintype "passive"))
      (node (ref "P1") (pin "1") (pinfunction "GND_1") (pintype "bidirectional"))
      (node (ref "P2") (pin "2") (pinfunction "GND_2") (pintype "input"))
      (node (ref "R22") (pin "1") (pinfunction "1_1") (pintype "passive"))
      (node (ref "R26") (pin "1") (pinfunction "1_1") (pintype "passive"))
      (node (ref "R27") (pin "1") (pinfunction "1_1") (pintype "passive"))
      (node (ref "R30") (pin "1") (pinfunction "1_1") (pintype "passive"))
      (node (ref "R37") (pin "1") (pinfunction "1_1") (pintype "passive"))
      (node (ref "R45") (pin "1") (pinfunction "1_1") (pintype "passive"))
      (node (ref "R47") (pin "1") (pinfunction "1_1") (pintype "passive"))
      (node (ref "R49") (pin "1") (pinfunction "1_1") (pintype "passive"))
      (node (ref "R6") (pin "1") (pinfunction "1_1") (pintype "passive"))
      (node (ref "R9") (pin "1") (pinfunction "1_1") (pintype "passive"))
      (node (ref "RST") (pin "1") (pinfunction "1_1") (pintype "bidirectional"))
      (node (ref "U1") (pin "19") (pinfunction "TESTEN_19") (pintype "passive"))
      (node (ref "U1") (pin "57") (pinfunction "GND_57") (pintype "passive"))
      (node (ref "U2") (pin "4") (pinfunction "GND_4") (pintype "passive"))
      (node (ref "U3") (pin "2") (pinfunction "GND_2") (pintype "power_in"))
      (node (ref "U3") (pin "8") (pinfunction "STBY_8") (pintype "input"))
      (node (ref "U5") (pin "2") (pinfunction "GND_2") (pintype "bidirectional"))
      (node (ref "U5") (pin "4") (pinfunction "GND1_4") (pintype "bidirectional"))
      (node (ref "U5") (pin "5") (pinfunction "GND2_5") (pintype "bidirectional"))
      (node (ref "U6") (pin "3") (pinfunction "GND_3") (pintype "power_in"))
      (node (ref "U7") (pin "13") (pinfunction "CLK_13") (pintype "input"))
      (node (ref "U7") (pin "18") (pinfunction "GND_18") (pintype "power_in"))
      (node (ref "U7") (pin "29") (pinfunction "EPAD_29") (pintype "passive"))
      (node (ref "U7") (pin "3") (pinfunction "GND_2_3") (pintype "power_in"))
      (node (ref "U7") (pin "7") (pinfunction "SPREAD_7") (pintype "input"))
      (node (ref "USB") (pin "1") (pinfunction "GND_1") (pintype "power_in"))
      (node (ref "USB") (pin "12") (pinfunction "GND2_12") (pintype "power_in"))
      (node (ref "USB") (pin "13") (pinfunction "SHLD_13") (pintype "passive"))
      (node (ref "USB") (pin "14") (pinfunction "SHLD_14") (pintype "passive"))
      (node (ref "USB") (pin "15") (pinfunction "SHLD_15") (pintype "passive"))
      (node (ref "USB") (pin "16") (pinfunction "SHLD_16") (pintype "passive"))
      (node (ref "USB") (pin "18") (pinfunction "SHLD_18") (pintype "passive"))
      (node (ref "USB") (pin "19") (pinfunction "SHLD_19") (pintype "passive"))
      (node (ref "USB") (pin "20") (pinfunction "SHLD_20") (pintype "passive"))
      (node (ref "USB") (pin "21") (pinfunction "SHLD_21") (pintype "passive"))
      (node (ref "USB") (pin "24") (pinfunction "SHLD_24") (pintype "passive"))
      (node (ref "USB") (pin "25") (pinfunction "SHLD_25") (pintype "passive"))
      (node (ref "USB") (pin "26") (pinfunction "SHLD_26") (pintype "passive"))
      (node (ref "USB") (pin "27") (pinfunction "SHLD_27") (pintype "passive"))
      (node (ref "USB") (pin "28") (pinfunction "SHLD_28") (pintype "passive"))
      (node (ref "USB") (pin "29") (pinfunction "SHLD_29") (pintype "passive"))
      (node (ref "USB") (pin "37") (pinfunction "SHLD_37") (pintype "passive"))
      (node (ref "USB") (pin "39") (pinfunction "SHLD_39") (pintype "passive"))
      (node (ref "USB") (pin "41") (pinfunction "SHLD_41") (pintype "passive"))
      (node (ref "USB") (pin "43") (pinfunction "SHLD_43") (pintype "passive"))
      (node (ref "X1") (pin "P$2") (pinfunction "GND_P$2") (pintype "bidirectional"))
      (node (ref "X1") (pin "P$4") (pinfunction "GND_P$4") (pintype "bidirectional"))
      (node (ref "X3") (pin "1") (pinfunction "S_1") (pintype "passive"))
    )
    (net (code "26") (name "HE0") (class "Default")
      (node (ref "HE0") (pin "P$1") (pinfunction "1_P$1") (pintype "bidirectional"))
      (node (ref "R37") (pin "2") (pinfunction "2_2") (pintype "passive"))
      (node (ref "U1") (pin "31") (pinfunction "GPIO20_31") (pintype "bidirectional"))
      (node (ref "U6") (pin "2") (pinfunction "A_2") (pintype "input"))
    )
    (net (code "27") (name "HE0_PWR") (class "Default")
      (node (ref "J3") (pin "1") (pinfunction "1_1") (pintype "passive"))
      (node (ref "M1") (pin "P$5") (pinfunction "D_P$5") (pintype "passive"))
      (node (ref "M1") (pin "P$6") (pinfunction "D_P$6") (pintype "passive"))
      (node (ref "M1") (pin "P$7") (pinfunction "D_P$7") (pintype "passive"))
      (node (ref "M1") (pin "P$8") (pinfunction "D_P$8") (pintype "passive"))
      (node (ref "M1") (pin "P$9") (pinfunction "D_P$9") (pintype "passive"))
    )
    (net (code "28") (name "I2C_SCL") (class "Default")
      (node (ref "U1") (pin "35") (pinfunction "GPIO23_35") (pintype "bidirectional"))
    )
    (net (code "29") (name "I2C_SDA") (class "Default")
      (node (ref "U1") (pin "34") (pinfunction "GPIO22_34") (pintype "bidirectional"))
    )
    (net (code "30") (name "Net-(BOOT-Pad2)") (class "Default")
      (node (ref "BOOT") (pin "2") (pinfunction "2_2") (pintype "bidirectional"))
      (node (ref "R12") (pin "2") (pinfunction "2_2") (pintype "passive"))
    )
    (net (code "31") (name "Net-(C23-Pad1)") (class "Default")
      (node (ref "C23") (pin "1") (pinfunction "1_1") (pintype "passive"))
      (node (ref "R7") (pin "1") (pinfunction "1_1") (pintype "passive"))
      (node (ref "R8") (pin "2") (pinfunction "2_2") (pintype "passive"))
    )
    (net (code "32") (name "Net-(D1-A)") (class "Default")
      (node (ref "D1") (pin "2") (pinfunction "A_2") (pintype "passive"))
      (node (ref "F1") (pin "1") (pinfunction "1_1") (pintype "passive"))
    )
    (net (code "33") (name "Net-(D2-I{slash}O1)") (class "Default")
      (node (ref "D2") (pin "1") (pinfunction "I/O1_2_1") (pintype "bidirectional"))
      (node (ref "D2") (pin "6") (pinfunction "I/O1_6") (pintype "bidirectional"))
      (node (ref "R10") (pin "1") (pinfunction "1_1") (pintype "passive"))
      (node (ref "USB") (pin "6") (pinfunction "AD+_6") (pintype "passive"))
      (node (ref "USB") (pin "7") (pinfunction "BD+_7") (pintype "passive"))
    )
    (net (code "34") (name "Net-(D2-I{slash}O2)") (class "Default")
      (node (ref "D2") (pin "3") (pinfunction "I/O2_2_3") (pintype "bidirectional"))
      (node (ref "D2") (pin "4") (pinfunction "I/O2_4") (pintype "bidirectional"))
      (node (ref "R11") (pin "1") (pinfunction "1_1") (pintype "passive"))
      (node (ref "USB") (pin "5") (pinfunction "BD-_5") (pintype "passive"))
      (node (ref "USB") (pin "8") (pinfunction "AD-_8") (pintype "passive"))
    )
    (net (code "35") (name "Net-(D2-VBUS)") (class "Default")
      (node (ref "D2") (pin "5") (pinfunction "VBUS_5") (pintype "power_in"))
      (node (ref "F1") (pin "2") (pinfunction "2_2") (pintype "passive"))
      (node (ref "SJ3") (pin "1") (pinfunction "1_1") (pintype "passive"))
    )
    (net (code "36") (name "Net-(D3-PadA)") (class "Default")
      (node (ref "D3") (pin "A") (pinfunction "A_A") (pintype "passive"))
      (node (ref "R15") (pin "1") (pinfunction "1_1") (pintype "passive"))
    )
    (net (code "37") (name "Net-(D4-Pad3)") (class "Default")
      (node (ref "D4") (pin "3") (pinfunction "3_3") (pintype "passive"))
      (node (ref "R35") (pin "2") (pinfunction "2_2") (pintype "passive"))
      (node (ref "R36") (pin "1") (pinfunction "1_1") (pintype "passive"))
    )
    (net (code "38") (name "Net-(D9-PadA)") (class "Default")
      (node (ref "D9") (pin "A") (pinfunction "A_A") (pintype "passive"))
      (node (ref "R28") (pin "1") (pinfunction "1_1") (pintype "passive"))
    )
    (net (code "39") (name "Net-(J3-Pad4)") (class "Default")
      (node (ref "J3") (pin "4") (pinfunction "4_4") (pintype "passive"))
      (node (ref "R33") (pin "1") (pinfunction "1_1") (pintype "passive"))
      (node (ref "R34") (pin "1") (pinfunction "1_1") (pintype "passive"))
      (node (ref "R35") (pin "1") (pinfunction "1_1") (pintype "passive"))
    )
    (net (code "40") (name "Net-(M1-G)") (class "Default")
      (node (ref "M1") (pin "P$4") (pinfunction "G_P$4") (pintype "passive"))
      (node (ref "R31") (pin "1") (pinfunction "1_1") (pintype "passive"))
    )
    (net (code "41") (name "Net-(M2-D)") (class "Default")
      (node (ref "M2") (pin "3") (pinfunction "D_3") (pintype "passive"))
      (node (ref "X5") (pin "1") (pinfunction "S_1") (pintype "passive"))
    )
    (net (code "42") (name "Net-(M2-G)") (class "Default")
      (node (ref "D6") (pin "3") (pinfunction "3_3") (pintype "passive"))
      (node (ref "M2") (pin "1") (pinfunction "G_1") (pintype "passive"))
      (node (ref "R44") (pin "1") (pinfunction "1_1") (pintype "passive"))
    )
    (net (code "43") (name "Net-(M3-D)") (class "Default")
      (node (ref "M3") (pin "3") (pinfunction "D_3") (pintype "passive"))
      (node (ref "X6") (pin "1") (pinfunction "S_1") (pintype "passive"))
    )
    (net (code "44") (name "Net-(M3-G)") (class "Default")
      (node (ref "D7") (pin "3") (pinfunction "3_3") (pintype "passive"))
      (node (ref "M3") (pin "1") (pinfunction "G_1") (pintype "passive"))
      (node (ref "R46") (pin "1") (pinfunction "1_1") (pintype "passive"))
    )
    (net (code "45") (name "Net-(M4-D)") (class "Default")
      (node (ref "M4") (pin "3") (pinfunction "D_3") (pintype "passive"))
      (node (ref "X7") (pin "1") (pinfunction "S_1") (pintype "passive"))
      (node (ref "X8") (pin "1") (pinfunction "S_1") (pintype "passive"))
    )
    (net (code "46") (name "Net-(M4-G)") (class "Default")
      (node (ref "D8") (pin "3") (pinfunction "3_3") (pintype "passive"))
      (node (ref "M4") (pin "1") (pinfunction "G_1") (pintype "passive"))
      (node (ref "R48") (pin "1") (pinfunction "1_1") (pintype "passive"))
    )
    (net (code "47") (name "Net-(P1-BOOT)") (class "Default")
      (node (ref "C20") (pin "1") (pinfunction "1_1") (pintype "passive"))
      (node (ref "P1") (pin "6") (pinfunction "BOOT_6") (pintype "bidirectional"))
    )
    (net (code "48") (name "Net-(P1-EN)") (class "Default")
      (node (ref "P1") (pin "5") (pinfunction "EN_5") (pintype "bidirectional"))
      (node (ref "R5") (pin "1") (pinfunction "1_1") (pintype "passive"))
      (node (ref "R6") (pin "2") (pinfunction "2_2") (pintype "passive"))
    )
    (net (code "49") (name "Net-(P1-FB)") (class "Default")
      (node (ref "C23") (pin "2") (pinfunction "2_2") (pintype "passive"))
      (node (ref "P1") (pin "4") (pinfunction "FB_4") (pintype "bidirectional"))
      (node (ref "R8") (pin "1") (pinfunction "1_1") (pintype "passive"))
      (node (ref "R9") (pin "2") (pinfunction "2_2") (pintype "passive"))
    )
    (net (code "50") (name "Net-(P1-SW)") (class "Default")
      (node (ref "C20") (pin "2") (pinfunction "2_2") (pintype "passive"))
      (node (ref "L1") (pin "1") (pinfunction "1_1") (pintype "bidirectional"))
      (node (ref "P1") (pin "2") (pinfunction "SW_2") (pintype "bidirectional"))
    )
    (net (code "51") (name "Net-(R1-Pad1)") (class "Default")
      (node (ref "R1") (pin "1") (pinfunction "1_1") (pintype "passive"))
      (node (ref "R2") (pin "2") (pinfunction "2_2") (pintype "passive"))
    )
    (net (code "52") (name "Net-(R16-Pad2)") (class "Default")
      (node (ref "R16") (pin "2") (pinfunction "2_2") (pintype "passive"))
      (node (ref "SJ1") (pin "2") (pinfunction "2_2") (pintype "passive"))
    )
    (net (code "53") (name "Net-(R34-Pad2)") (class "Default")
      (node (ref "R34") (pin "2") (pinfunction "2_2") (pintype "passive"))
      (node (ref "SJ2") (pin "1") (pinfunction "1_1") (pintype "passive"))
    )
    (net (code "54") (name "Net-(U1-GPIO2)") (class "Default")
      (node (ref "R28") (pin "2") (pinfunction "2_2") (pintype "passive"))
      (node (ref "U1") (pin "4") (pinfunction "GPIO2_4") (pintype "bidirectional"))
    )
    (net (code "55") (name "Net-(U3-CANH)") (class "Default")
      (node (ref "L2") (pin "1") (pinfunction "1_1") (pintype "passive"))
      (node (ref "U3") (pin "7") (pinfunction "CANH_7") (pintype "output"))
    )
    (net (code "56") (name "Net-(U3-CANL)") (class "Default")
      (node (ref "L2") (pin "2") (pinfunction "2_2") (pintype "passive"))
      (node (ref "U3") (pin "6") (pinfunction "CANL_6") (pintype "output"))
    )
    (net (code "57") (name "Net-(U6-Y)") (class "Default")
      (node (ref "R30") (pin "2") (pinfunction "2_2") (pintype "passive"))
      (node (ref "R31") (pin "2") (pinfunction "2_2") (pintype "passive"))
      (node (ref "U6") (pin "4") (pinfunction "Y_4") (pintype "output"))
    )
    (net (code "58") (name "Net-(U7-5VOUT)") (class "Default")
      (node (ref "C32") (pin "2") (pinfunction "2_2") (pintype "passive"))
      (node (ref "U7") (pin "8") (pinfunction "5VOUT_8") (pintype "output"))
    )
    (net (code "59") (name "Net-(U7-CPI)") (class "Default")
      (node (ref "C28") (pin "1") (pinfunction "1_1") (pintype "passive"))
      (node (ref "U7") (pin "5") (pinfunction "CPI_5") (pintype "input"))
    )
    (net (code "60") (name "Net-(U7-CPO)") (class "Default")
      (node (ref "C28") (pin "2") (pinfunction "2_2") (pintype "passive"))
      (node (ref "U7") (pin "4") (pinfunction "CPO_4") (pintype "output"))
    )
    (net (code "61") (name "Net-(U7-DIR)") (class "Default")
      (node (ref "R25") (pin "2") (pinfunction "2_2") (pintype "passive"))
      (node (ref "U7") (pin "19") (pinfunction "DIR_19") (pintype "input"))
    )
    (net (code "62") (name "Net-(U7-ENN)") (class "Default")
      (node (ref "R21") (pin "2") (pinfunction "2_2") (pintype "passive"))
      (node (ref "R23") (pin "1") (pinfunction "1_1") (pintype "passive"))
      (node (ref "U7") (pin "2") (pinfunction "ENN_2") (pintype "input"))
    )
    (net (code "63") (name "Net-(U7-STEP)") (class "Default")
      (node (ref "R24") (pin "2") (pinfunction "2_2") (pintype "passive"))
      (node (ref "U7") (pin "16") (pinfunction "STEP_16") (pintype "input"))
    )
    (net (code "64") (name "Net-(U7-VCP)") (class "Default")
      (node (ref "C29") (pin "2") (pinfunction "2_2") (pintype "passive"))
      (node (ref "U7") (pin "6") (pinfunction "VCP_6") (pintype "power_in"))
    )
    (net (code "65") (name "Net-(X1-P2)") (class "Default")
      (node (ref "C2") (pin "2") (pinfunction "2_2") (pintype "passive"))
      (node (ref "R3") (pin "1") (pinfunction "1_1") (pintype "passive"))
      (node (ref "X1") (pin "P$3") (pinfunction "P2_P$3") (pintype "bidirectional"))
    )
    (net (code "66") (name "Net-(X3B-S)") (class "Default")
      (node (ref "R40") (pin "2") (pinfunction "2_2") (pintype "passive"))
      (node (ref "R41") (pin "2") (pinfunction "2_2") (pintype "passive"))
      (node (ref "X3") (pin "2") (pinfunction "S_2") (pintype "passive"))
    )
    (net (code "67") (name "OSC_IN") (class "Default")
      (node (ref "C1") (pin "1") (pinfunction "1_1") (pintype "passive"))
      (node (ref "R4") (pin "2") (pinfunction "2_2") (pintype "passive"))
      (node (ref "U1") (pin "20") (pinfunction "XIN_20") (pintype "passive"))
      (node (ref "X1") (pin "P$1") (pinfunction "P1_P$1") (pintype "bidirectional"))
    )
    (net (code "68") (name "OSC_OUT") (class "Default")
      (node (ref "R3") (pin "2") (pinfunction "2_2") (pintype "passive"))
      (node (ref "R4") (pin "1") (pinfunction "1_1") (pintype "passive"))
      (node (ref "U1") (pin "21") (pinfunction "XOUT_21") (pintype "output"))
    )
    (net (code "69") (name "QSPI_SCK") (class "Default")
      (node (ref "U1") (pin "52") (pinfunction "QSPI_SCLK_52") (pintype "passive"))
      (node (ref "U2") (pin "6") (pinfunction "CLK_6") (pintype "passive"))
    )
    (net (code "70") (name "QSPI_SD0") (class "Default")
      (node (ref "U1") (pin "53") (pinfunction "QSPI_SD0_53") (pintype "bidirectional"))
      (node (ref "U2") (pin "5") (pinfunction "DI_(IO0)_5") (pintype "passive"))
    )
    (net (code "71") (name "QSPI_SD1") (class "Default")
      (node (ref "U1") (pin "55") (pinfunction "QSPI_SD1_55") (pintype "bidirectional"))
      (node (ref "U2") (pin "2") (pinfunction "DO_(IO1)_2") (pintype "passive"))
    )
    (net (code "72") (name "QSPI_SD2") (class "Default")
      (node (ref "U1") (pin "54") (pinfunction "QSPI_SD2_54") (pintype "bidirectional"))
      (node (ref "U2") (pin "3") (pinfunction "/WP_(IO2)_3") (pintype "passive"))
    )
    (net (code "73") (name "QSPI_SD3") (class "Default")
      (node (ref "U1") (pin "51") (pinfunction "QSPI_SD3_51") (pintype "bidirectional"))
      (node (ref "U2") (pin "7") (pinfunction "/RESET_(IO3)_7") (pintype "passive"))
    )
    (net (code "74") (name "QSPI_SS") (class "Default")
      (node (ref "R12") (pin "1") (pinfunction "1_1") (pintype "passive"))
      (node (ref "R13") (pin "1") (pinfunction "1_1") (pintype "passive"))
      (node (ref "U1") (pin "56") (pinfunction "QSPI_SS_N_56") (pintype "passive"))
      (node (ref "U2") (pin "1") (pinfunction "/CS_1") (pintype "passive"))
    )
    (net (code "75") (name "RESET") (class "Default")
      (node (ref "C25") (pin "2") (pinfunction "2_2") (pintype "passive"))
      (node (ref "R14") (pin "1") (pinfunction "1_1") (pintype "passive"))
      (node (ref "RST") (pin "2") (pinfunction "2_2") (pintype "bidirectional"))
      (node (ref "U1") (pin "26") (pinfunction "RUN_26") (pintype "passive"))
    )
    (net (code "76") (name "SPI0_CS") (class "Default")
      (node (ref "U1") (pin "28") (pinfunction "GPIO17_28") (pintype "bidirectional"))
    )
    (net (code "77") (name "SPI0_MISO") (class "Default")
      (node (ref "U1") (pin "27") (pinfunction "GPIO16_27") (pintype "bidirectional"))
    )
    (net (code "78") (name "SPI0_MOSI") (class "Default")
      (node (ref "U1") (pin "30") (pinfunction "GPIO19_30") (pintype "bidirectional"))
    )
    (net (code "79") (name "SPI0_SCK") (class "Default")
      (node (ref "U1") (pin "29") (pinfunction "GPIO18_29") (pintype "bidirectional"))
    )
    (net (code "80") (name "SPI1_CS") (class "Default")
      (node (ref "R19") (pin "1") (pinfunction "1_1") (pintype "passive"))
      (node (ref "U1") (pin "16") (pinfunction "GPIO13_16") (pintype "bidirectional"))
      (node (ref "U5") (pin "7") (pinfunction "~{CS}_7") (pintype "bidirectional"))
    )
    (net (code "81") (name "SPI1_MISO") (class "Default")
      (node (ref "R18") (pin "1") (pinfunction "1_1") (pintype "passive"))
      (node (ref "U1") (pin "15") (pinfunction "GPIO12_15") (pintype "bidirectional"))
      (node (ref "U5") (pin "12") (pinfunction "SDO/ALT_ADDRESS_12") (pintype "bidirectional"))
    )
    (net (code "82") (name "SPI1_MOSI") (class "Default")
      (node (ref "R17") (pin "1") (pinfunction "1_1") (pintype "passive"))
      (node (ref "U1") (pin "18") (pinfunction "GPIO15_18") (pintype "bidirectional"))
      (node (ref "U5") (pin "13") (pinfunction "SDA/SDI/SDIO_13") (pintype "bidirectional"))
    )
    (net (code "83") (name "SPI1_SCK") (class "Default")
      (node (ref "R20") (pin "1") (pinfunction "1_1") (pintype "passive"))
      (node (ref "U1") (pin "17") (pinfunction "GPIO14_17") (pintype "bidirectional"))
      (node (ref "U5") (pin "14") (pinfunction "SCL/SCLK_14") (pintype "bidirectional"))
    )
    (net (code "84") (name "SWCLK") (class "Default")
      (node (ref "U1") (pin "24") (pinfunction "SWCLK_24") (pintype "passive"))
    )
    (net (code "85") (name "SWDIO") (class "Default")
      (node (ref "U1") (pin "25") (pinfunction "SWDIO_25") (pintype "passive"))
    )
    (net (code "86") (name "TH0") (class "Default")
      (node (ref "C40") (pin "1") (pinfunction "1_1") (pintype "passive"))
      (node (ref "R36") (pin "2") (pinfunction "2_2") (pintype "passive"))
      (node (ref "TH0") (pin "P$1") (pinfunction "1_P$1") (pintype "bidirectional"))
      (node (ref "U1") (pin "38") (pinfunction "GPIO26/ADC0_38") (pintype "bidirectional"))
    )
    (net (code "87") (name "USB_N") (class "Default")
      (node (ref "IO1") (pin "P$1") (pinfunction "1_P$1") (pintype "bidirectional"))
      (node (ref "R11") (pin "2") (pinfunction "2_2") (pintype "passive"))
      (node (ref "U1") (pin "46") (pinfunction "USB_DM_46") (pintype "passive"))
    )
    (net (code "88") (name "USB_P") (class "Default")
      (node (ref "IO2") (pin "P$1") (pinfunction "1_P$1") (pintype "bidirectional"))
      (node (ref "R10") (pin "2") (pinfunction "2_2") (pintype "passive"))
      (node (ref "U1") (pin "47") (pinfunction "USB_DP_47") (pintype "passive"))
    )
    (net (code "89") (name "VBUS") (class "Default")
      (node (ref "SJ3") (pin "2") (pinfunction "2_2") (pintype "passive"))
      (node (ref "USB") (pin "11") (pinfunction "VBUS2_11") (pintype "power_in"))
      (node (ref "USB") (pin "2") (pinfunction "VBUS_2") (pintype "power_in"))
    )
    (net (code "90") (name "unconnected-(P2-NC-Pad4)") (class "Default")
      (node (ref "P2") (pin "4") (pinfunction "NC_4") (pintype "no_connect"))
    )
    (net (code "91") (name "unconnected-(U1-GPIO3-Pad5)") (class "Default")
      (node (ref "U1") (pin "5") (pinfunction "GPIO3_5") (pintype "bidirectional"))
    )
    (net (code "92") (name "unconnected-(U1-GPIO4-Pad6)") (class "Default")
      (node (ref "U1") (pin "6") (pinfunction "GPIO4_6") (pintype "bidirectional"))
    )
    (net (code "93") (name "unconnected-(U1-GPIO5-Pad7)") (class "Default")
      (node (ref "U1") (pin "7") (pinfunction "GPIO5_7") (pintype "bidirectional"))
    )
    (net (code "94") (name "unconnected-(U1-GPIO6-Pad8)") (class "Default")
      (node (ref "U1") (pin "8") (pinfunction "GPIO6_8") (pintype "bidirectional"))
    )
    (net (code "95") (name "unconnected-(U1-GPIO11-Pad14)") (class "Default")
      (node (ref "U1") (pin "14") (pinfunction "GPIO11_14") (pintype "bidirectional"))
    )
    (net (code "96") (name "unconnected-(U1-GPIO29{slash}ADC3-Pad41)") (class "Default")
      (node (ref "U1") (pin "41") (pinfunction "GPIO29/ADC3_41") (pintype "bidirectional"))
    )
    (net (code "97") (name "unconnected-(U5-INT1-Pad8)") (class "Default")
      (node (ref "U5") (pin "8") (pinfunction "INT1_8") (pintype "bidirectional"))
    )
    (net (code "98") (name "unconnected-(U5-INT2-Pad9)") (class "Default")
      (node (ref "U5") (pin "9") (pinfunction "INT2_9") (pintype "bidirectional"))
    )
    (net (code "99") (name "unconnected-(U5-NC-Pad10)") (class "Default")
      (node (ref "U5") (pin "10") (pinfunction "NC_10") (pintype "bidirectional"))
    )
    (net (code "100") (name "unconnected-(U5-RESERVED-Pad3)") (class "Default")
      (node (ref "U5") (pin "3") (pinfunction "RESERVED_3") (pintype "bidirectional"))
    )
    (net (code "101") (name "unconnected-(U5-RESERVED1-Pad11)") (class "Default")
      (node (ref "U5") (pin "11") (pinfunction "RESERVED1_11") (pintype "bidirectional"))
    )
    (net (code "102") (name "unconnected-(U6-NC-Pad1)") (class "Default")
      (node (ref "U6") (pin "1") (pinfunction "NC_1") (pintype "passive"))
    )
    (net (code "103") (name "unconnected-(U7-INDEX-Pad12)") (class "Default")
      (node (ref "U7") (pin "12") (pinfunction "INDEX_12") (pintype "output"))
    )
    (net (code "104") (name "unconnected-(U7-MS1_AD0-Pad9)") (class "Default")
      (node (ref "U7") (pin "9") (pinfunction "MS1_AD0_9") (pintype "input"))
    )
    (net (code "105") (name "unconnected-(U7-MS2_AD1-Pad10)") (class "Default")
      (node (ref "U7") (pin "10") (pinfunction "MS2_AD1_10") (pintype "input"))
    )
    (net (code "106") (name "unconnected-(U7-NC-Pad25)") (class "Default")
      (node (ref "U7") (pin "25") (pinfunction "NC_25") (pintype "no_connect"))
    )
    (net (code "107") (name "unconnected-(U7-STDBY-Pad20)") (class "Default")
      (node (ref "U7") (pin "20") (pinfunction "STDBY_20") (pintype "input"))
    )
    (net (code "108") (name "unconnected-(U7-VREF-Pad17)") (class "Default")
      (node (ref "U7") (pin "17") (pinfunction "VREF_17") (pintype "input"))
    )
    (net (code "109") (name "unconnected-(USB-CC1-Pad3)") (class "Default")
      (node (ref "USB") (pin "3") (pinfunction "CC1_3") (pintype "passive"))
    )
    (net (code "110") (name "unconnected-(USB-CC2-Pad9)") (class "Default")
      (node (ref "USB") (pin "9") (pinfunction "CC2_9") (pintype "passive"))
    )
    (net (code "111") (name "unconnected-(USB-SBU1-Pad10)") (class "Default")
      (node (ref "USB") (pin "10") (pinfunction "SBU1_10") (pintype "passive"))
    )
    (net (code "112") (name "unconnected-(USB-SBU2-Pad4)") (class "Default")
      (node (ref "USB") (pin "4") (pinfunction "SBU2_4") (pintype "passive"))
    )
  )
)
